# C_76p593.net
KiCad netlist of a schematic drawn in Altium Designer
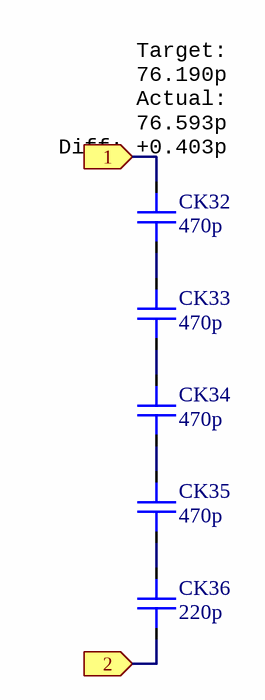
[diagram p0: C_76p593.SchDoc]

(export (version "E")
  (design (tool "Eeschema 10.0.6"))
  (components
    (comp (ref "CK32")
      (value "470p")
      (footprint "CAPC1005X06N(SMC0402)")
      (description "C; 470p; 50V; 1%; NP0/C0G; ??;")
      (fields (field (name "MANUFACTURER") "Kemet: C0402C471F5GAC7867;;Murata: GRM1555C1H471FA01D"))
      (libsource (lib "altium_sql") (part "CK"))
    )
    (comp (ref "CK33")
      (value "470p")
      (footprint "CAPC1005X06N(SMC0402)")
      (description "C; 470p; 50V; 1%; NP0/C0G; ??;")
      (fields (field (name "MANUFACTURER") "Kemet: C0402C471F5GAC7867;;Murata: GRM1555C1H471FA01D"))
      (libsource (lib "altium_sql") (part "CK"))
    )
    (comp (ref "CK34")
      (value "470p")
      (footprint "CAPC1005X06N(SMC0402)")
      (description "C; 470p; 50V; 1%; NP0/C0G; ??;")
      (fields (field (name "MANUFACTURER") "Kemet: C0402C471F5GAC7867;;Murata: GRM1555C1H471FA01D"))
      (libsource (lib "altium_sql") (part "CK"))
    )
    (comp (ref "CK35")
      (value "470p")
      (footprint "CAPC1005X06N(SMC0402)")
      (description "C; 470p; 50V; 1%; NP0/C0G; ??;")
      (fields (field (name "MANUFACTURER") "Kemet: C0402C471F5GAC7867;;Murata: GRM1555C1H471FA01D"))
      (libsource (lib "altium_sql") (part "CK"))
    )
    (comp (ref "CK36")
      (value "220p")
      (footprint "CAPC1005X06N(SMC0402)")
      (description "C; 220p; 50V; 1%; NP0/C0G; ??;")
      (fields (field (name "MANUFACTURER") "YAGEO: CC0402FRNPO9BN221"))
      (libsource (lib "altium_sql") (part "CK"))
    )
  )
  (nets
    (net (code "1") (name "/1") (class "Default")
      (node (ref "CK32") (pin "1") (pinfunction "1_1") (pintype "passive"))
    )
    (net (code "2") (name "/2") (class "Default")
      (node (ref "CK36") (pin "2") (pinfunction "2_2") (pintype "passive"))
    )
    (net (code "3") (name "Net-(CK32-Pad2)") (class "Default")
      (node (ref "CK32") (pin "2") (pinfunction "2_2") (pintype "passive"))
      (node (ref "CK33") (pin "1") (pinfunction "1_1") (pintype "passive"))
    )
    (net (code "4") (name "Net-(CK33-Pad2)") (class "Default")
      (node (ref "CK33") (pin "2") (pinfunction "2_2") (pintype "passive"))
      (node (ref "CK34") (pin "1") (pinfunction "1_1") (pintype "passive"))
    )
    (net (code "5") (name "Net-(CK34-Pad2)") (class "Default")
      (node (ref "CK34") (pin "2") (pinfunction "2_2") (pintype "passive"))
      (node (ref "CK35") (pin "1") (pinfunction "1_1") (pintype "passive"))
    )
    (net (code "6") (name "Net-(CK35-Pad2)") (class "Default")
      (node (ref "CK35") (pin "2") (pinfunction "2_2") (pintype "passive"))
      (node (ref "CK36") (pin "1") (pinfunction "1_1") (pintype "passive"))
    )
  )
)
